# USB-C.net
KiCad netlist of a schematic drawn in Altium Designer
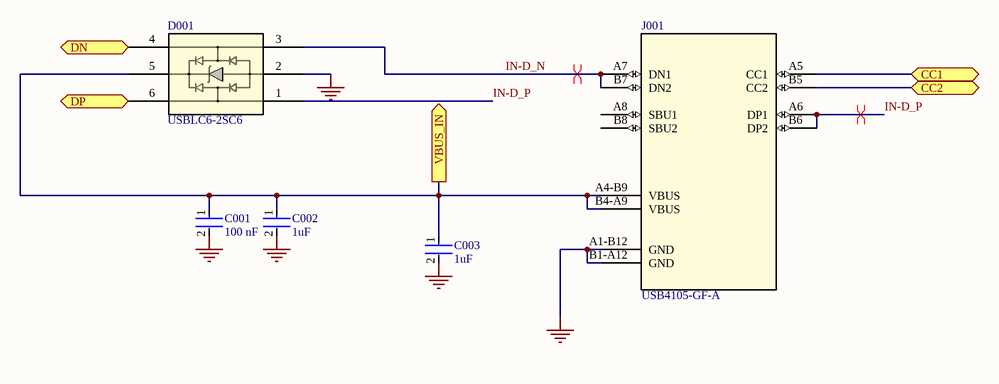
[diagram p0: USB-C.SchDoc]

(export (version "E")
  (design (tool "Eeschema 10.0.6"))
  (components
    (comp (ref "C001")
      (value "100 nF")
      (footprint "FP-CC0201-BA-MFG")
      (description "CAP CER 0.1UF 16V X5R 0201")
      (fields
        (field (name "MANUFACTURER PART NUMBER") "CC0201KRX5R7BB104")
        (field (name "MANUFACTURER") "Yageo")
      )
      (libsource (lib "Altium Content Vault") (part "11868f565c42a9108669ba33697ecf6"))
    )
    (comp (ref "C002")
      (value "1uF")
      (footprint "FP-CL10-IPC_C")
      (description "Cap Ceramic 1uF 10V X5R ±10% Pad SMD 0603 +85°C T/R")
      (fields (field (name "TOLERANCE") "10%") (field (name "VOLTAGE") "10V"))
      (libsource (lib "Altium Content Vault") (part "b4654b650e69147ec39a6b967a45e02"))
    )
    (comp (ref "C003")
      (value "1uF")
      (footprint "FP-CL10-IPC_C")
      (description "Cap Ceramic 1uF 10V X5R ±10% Pad SMD 0603 +85°C T/R")
      (fields (field (name "TOLERANCE") "10%") (field (name "VOLTAGE") "10V"))
      (libsource (lib "Altium Content Vault") (part "b4654b650e69147ec39a6b967a45e02"))
    )
    (comp (ref "D001")
      (value "USBLC6-2SC6")
      (footprint "SOT23-6L_STM")
      (description "5A 17V 6V Unidirectional 5.25V SOT-23-6 ESD and Surge Protection (TVS/ESD) ROHS")
      (fields (field (name "MANUFACTURER") "STMicroelectronics"))
      (libsource (lib "Watch_Components") (part "USBLC6-2SC6"))
    )
    (comp (ref "J001")
      (value "USB4105-GF-A")
      (footprint "USB4105_GCT")
      (description "USB Connector, 24 Contact(s), Female, Right Angle, Solder Terminal, Locking, Receptacle")
      (fields (field (name "MANUFACTURER") "Global Connector Technology"))
      (libsource (lib "Watch_Components") (part "USB4105-GF-A"))
    )
  )
  (nets
    (net (code "1") (name "/CC1") (class "Default")
      (node (ref "J001") (pin "A5") (pinfunction "CC1_A5") (pintype "bidirectional"))
    )
    (net (code "2") (name "/CC2") (class "Default")
      (node (ref "J001") (pin "B5") (pinfunction "CC2_B5") (pintype "bidirectional"))
    )
    (net (code "3") (name "/DN") (class "Default")
      (node (ref "D001") (pin "4") (pinfunction "4_4") (pintype "passive"))
    )
    (net (code "4") (name "/DP") (class "Default")
      (node (ref "D001") (pin "6") (pinfunction "6_6") (pintype "passive"))
    )
    (net (code "5") (name "/IN-D_N") (class "Default")
      (node (ref "D001") (pin "3") (pinfunction "3_3") (pintype "passive"))
      (node (ref "J001") (pin "A7") (pinfunction "DN1_A7") (pintype "bidirectional"))
      (node (ref "J001") (pin "B7") (pinfunction "DN2_B7") (pintype "bidirectional"))
    )
    (net (code "6") (name "/IN-D_P") (class "Default")
      (node (ref "D001") (pin "1") (pinfunction "1_1") (pintype "passive"))
      (node (ref "J001") (pin "A6") (pinfunction "DP1_A6") (pintype "bidirectional"))
      (node (ref "J001") (pin "B6") (pinfunction "DP2_B6") (pintype "bidirectional"))
    )
    (net (code "7") (name "/VBUS_IN") (class "Default")
      (node (ref "C001") (pin "1") (pinfunction "1_1") (pintype "passive"))
      (node (ref "C002") (pin "1") (pinfunction "1_1") (pintype "passive"))
      (node (ref "C003") (pin "1") (pinfunction "1_1") (pintype "passive"))
      (node (ref "D001") (pin "5") (pinfunction "5_5") (pintype "passive"))
      (node (ref "J001") (pin "A4-B9") (pinfunction "VBUS_A4-B9") (pintype "passive"))
      (node (ref "J001") (pin "B4-A9") (pinfunction "VBUS_B4-A9") (pintype "passive"))
    )
    (net (code "8") (name "GND") (class "Default")
      (node (ref "C001") (pin "2") (pinfunction "2_2") (pintype "passive"))
      (node (ref "C002") (pin "2") (pinfunction "2_2") (pintype "passive"))
      (node (ref "C003") (pin "2") (pinfunction "2_2") (pintype "passive"))
      (node (ref "D001") (pin "2") (pinfunction "2_2") (pintype "passive"))
      (node (ref "J001") (pin "A1-B12") (pinfunction "GND_A1-B12") (pintype "power_in"))
      (node (ref "J001") (pin "B1-A12") (pinfunction "GND_B1-A12") (pintype "power_in"))
    )
    (net (code "9") (name "unconnected-(J001-SBU1-PadA8)") (class "Default")
      (node (ref "J001") (pin "A8") (pinfunction "SBU1_A8") (pintype "bidirectional"))
    )
    (net (code "10") (name "unconnected-(J001-SBU2-PadB8)") (class "Default")
      (node (ref "J001") (pin "B8") (pinfunction "SBU2_B8") (pintype "bidirectional"))
    )
  )
)
